# design.net
KiCad netlist of a schematic drawn in EasyEDA Pro
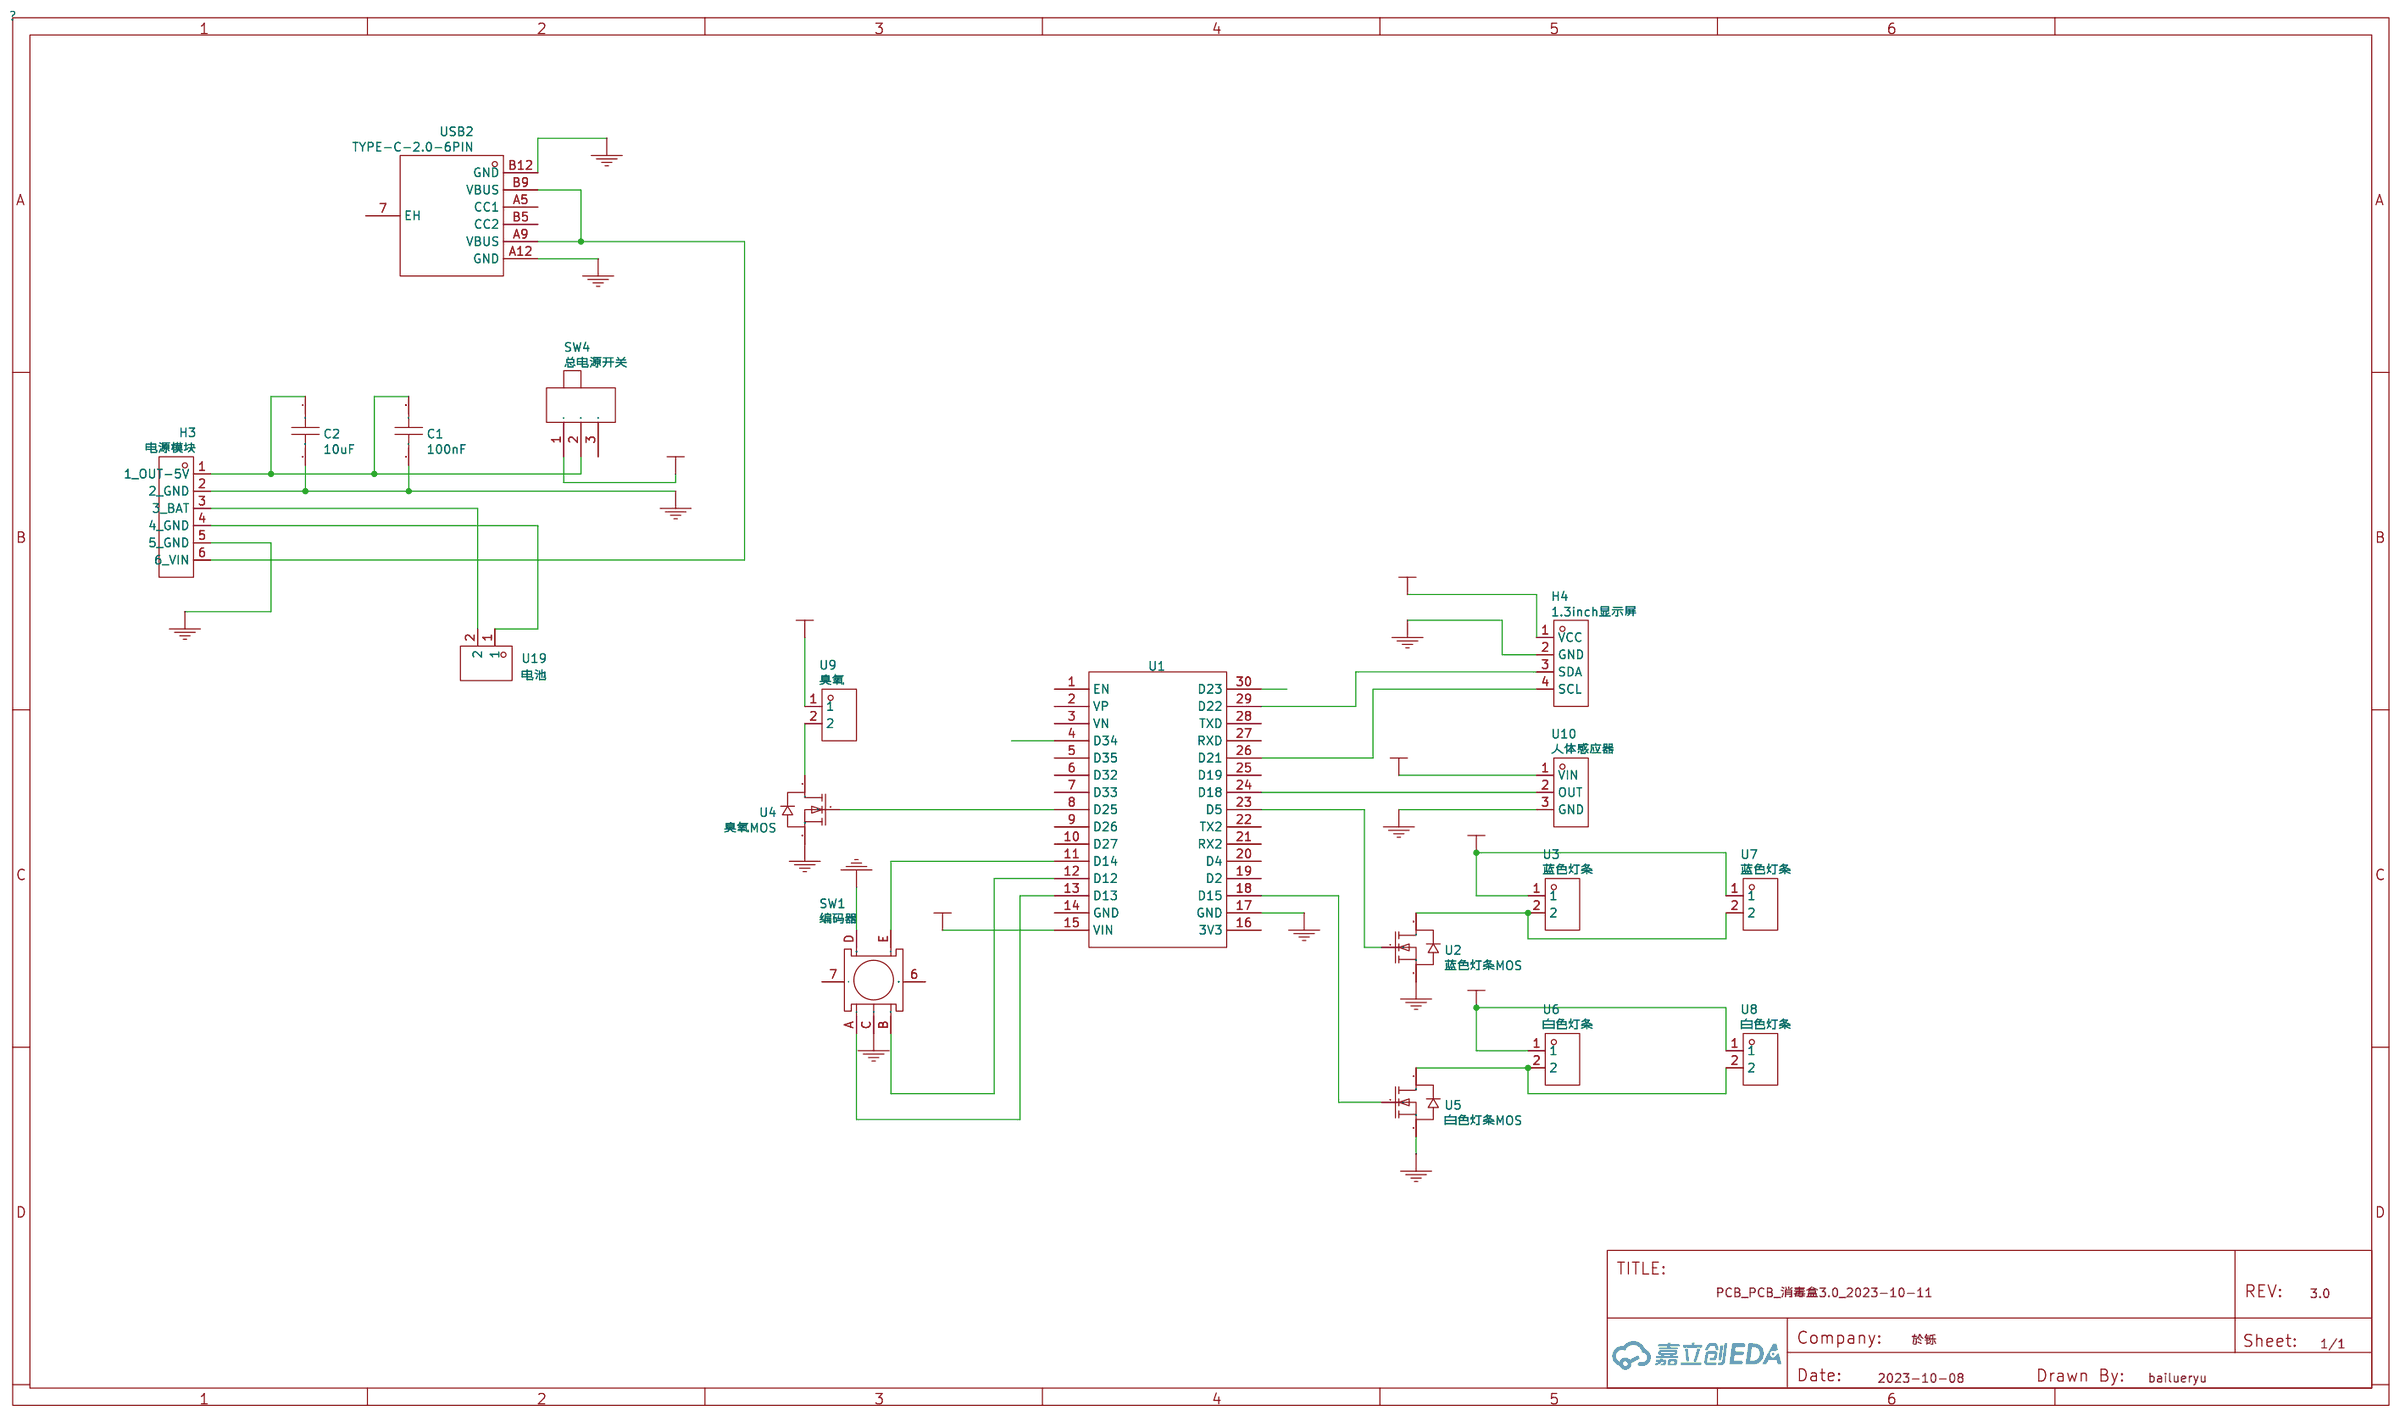
[diagram p0: schematic sheet]

(export (version "E")
  (design (tool "Eeschema 10.0.6"))
  (components
    (comp (ref "C1")
      (value "100nF")
      (footprint "easyedapro:C0603")
      (fields
        (field (name "Manufacturer Part") "MC0603B104K500N8RH")
        (field (name "Manufacturer") "Sunway(信维通信)")
      )
      (libsource (lib "easyedapro") (part "100nF"))
    )
    (comp (ref "C2")
      (value "10uF")
      (footprint "easyedapro:C0603")
      (fields (field (name "Manufacturer") "SAMSUNG(三星)"))
      (libsource (lib "easyedapro") (part "10uF"))
    )
    (comp (ref "H3")
      (value "电源模块")
      (footprint "easyedapro:HDR-TH_6P-P2.54-V-M")
      (fields (field (name "Manufacturer Part") "PZ254V-11-06P") (field (name "Manufacturer") "XFCN(兴飞)"))
      (libsource (lib "easyedapro") (part "电源模块"))
    )
    (comp (ref "H4")
      (value "1.3inch显示屏")
      (footprint "easyedapro:HDR-TH_4P-P2.54-V-M")
      (fields
        (field (name "Manufacturer Part") "KH-2.54PH180-1X4P-L11.5")
        (field (name "Manufacturer") "kinghelm(金航标)")
      )
      (libsource (lib "easyedapro") (part "1.3inch显示屏"))
    )
    (comp (ref "SW1")
      (value "编码器")
      (footprint "easyedapro:SW-TH_EC11E18244A5")
      (fields (field (name "Manufacturer Part") "EC11E18244A5") (field (name "Manufacturer") "ALPS Electric"))
      (libsource (lib "easyedapro") (part "编码器"))
    )
    (comp (ref "SW4")
      (value "总电源开关")
      (footprint "easyedapro:SW-TH_MK-12D18-G040")
      (fields (field (name "Manufacturer Part") "MK-12D18-G020") (field (name "Manufacturer") "G-Switch(品赞)"))
      (libsource (lib "easyedapro") (part "总电源开关"))
    )
    (comp (ref "U1")
      (value "NO")
      (footprint "easyedapro:ESP-WROOM-32")
      (libsource (lib "easyedapro") (part "NO"))
    )
    (comp (ref "U2")
      (value "蓝色灯条MOS")
      (footprint "easyedapro:SOT-23-3_L2.9-W1.3-P1.90-LS2.4-BR")
      (fields (field (name "Manufacturer Part") "5N10") (field (name "Manufacturer") "GOODWORK(固得沃克)"))
      (libsource (lib "easyedapro") (part "蓝色灯条MOS"))
    )
    (comp (ref "U3")
      (value "蓝色灯条")
      (footprint "easyedapro:HDR-TH_2P-P2.00-V-M")
      (fields
        (field (name "Manufacturer Part") "DS1025-01-1x2P8BV1-B")
        (field (name "Manufacturer") "CONNFLY")
      )
      (libsource (lib "easyedapro") (part "蓝色灯条"))
    )
    (comp (ref "U4")
      (value "臭氧MOS")
      (footprint "easyedapro:SOT-23-3_L2.9-W1.3-P1.90-LS2.4-BR")
      (fields (field (name "Manufacturer Part") "5N10") (field (name "Manufacturer") "GOODWORK(固得沃克)"))
      (libsource (lib "easyedapro") (part "臭氧MOS"))
    )
    (comp (ref "U5")
      (value "白色灯条MOS")
      (footprint "easyedapro:SOT-23-3_L2.9-W1.3-P1.90-LS2.4-BR")
      (fields (field (name "Manufacturer Part") "5N10") (field (name "Manufacturer") "GOODWORK(固得沃克)"))
      (libsource (lib "easyedapro") (part "白色灯条MOS"))
    )
    (comp (ref "U6")
      (value "白色灯条")
      (footprint "easyedapro:HDR-TH_2P-P2.00-V-M")
      (fields
        (field (name "Manufacturer Part") "DS1025-01-1x2P8BV1-B")
        (field (name "Manufacturer") "CONNFLY")
      )
      (libsource (lib "easyedapro") (part "白色灯条"))
    )
    (comp (ref "U7")
      (value "蓝色灯条")
      (footprint "easyedapro:HDR-TH_2P-P2.00-V-M")
      (fields
        (field (name "Manufacturer Part") "DS1025-01-1x2P8BV1-B")
        (field (name "Manufacturer") "CONNFLY")
      )
      (libsource (lib "easyedapro") (part "蓝色灯条"))
    )
    (comp (ref "U8")
      (value "白色灯条")
      (footprint "easyedapro:HDR-TH_2P-P2.00-V-M")
      (fields
        (field (name "Manufacturer Part") "DS1025-01-1x2P8BV1-B")
        (field (name "Manufacturer") "CONNFLY")
      )
      (libsource (lib "easyedapro") (part "白色灯条"))
    )
    (comp (ref "U9")
      (value "臭氧")
      (footprint "easyedapro:HDR-TH_2P-P2.00-V-M")
      (fields
        (field (name "Manufacturer Part") "DS1025-01-1x2P8BV1-B")
        (field (name "Manufacturer") "CONNFLY")
      )
      (libsource (lib "easyedapro") (part "臭氧"))
    )
    (comp (ref "U10")
      (value "人体感应器")
      (footprint "easyedapro:HDR-TH_3P-P2.00-V-M")
      (fields
        (field (name "Manufacturer Part") "DS1025-01-1x3P8BV1-B")
        (field (name "Manufacturer") "CONNFLY")
      )
      (libsource (lib "easyedapro") (part "人体感应器"))
    )
    (comp (ref "U19")
      (value "电池")
      (footprint "easyedapro:HDR-TH_2P-P2.00-V-M")
      (fields
        (field (name "Manufacturer Part") "DS1025-01-1x2P8BV1-B")
        (field (name "Manufacturer") "CONNFLY")
      )
      (libsource (lib "easyedapro") (part "臭氧"))
    )
    (comp (ref "USB2")
      (value "TYPE-C-2.0-6PIN")
      (footprint "easyedapro:TYPE-C-SMD_TYPE-C-6P-2")
      (fields (field (name "Manufacturer Part") "Type-C-2.0-6Pin") (field (name "Manufacturer") "CIKI(皓富)"))
      (libsource (lib "easyedapro") (part "TYPE-C-2.0-6PIN"))
    )
  )
  (nets
    (net (code "1") (name "GND") (class "Default")
      (node (ref "C1") (pin "1") (pinfunction "1_1") (pintype "input"))
      (node (ref "C2") (pin "2") (pinfunction "2_2") (pintype "input"))
      (node (ref "H3") (pin "2") (pinfunction "2_GND_2") (pintype "input"))
      (node (ref "H3") (pin "5") (pinfunction "5_GND_5") (pintype "input"))
      (node (ref "H4") (pin "2") (pinfunction "GND_2") (pintype "input"))
      (node (ref "SW1") (pin "C") (pinfunction "C_C") (pintype "input"))
      (node (ref "SW1") (pin "D") (pinfunction "D_D") (pintype "input"))
      (node (ref "U1") (pin "17") (pinfunction "GND_17") (pintype "input"))
      (node (ref "U10") (pin "3") (pinfunction "GND_3") (pintype "input"))
      (node (ref "U2") (pin "2") (pinfunction "S_2") (pintype "input"))
      (node (ref "U4") (pin "2") (pinfunction "S_2") (pintype "input"))
      (node (ref "U5") (pin "2") (pinfunction "S_2") (pintype "input"))
      (node (ref "USB2") (pin "A12") (pinfunction "GND_A12") (pintype "input"))
      (node (ref "USB2") (pin "B12") (pinfunction "GND_B12") (pintype "input"))
    )
    (net (code "2") (name "Net-(H3-1_OUT-5V)") (class "Default")
      (node (ref "C1") (pin "2") (pinfunction "2_2") (pintype "input"))
      (node (ref "C2") (pin "1") (pinfunction "1_1") (pintype "input"))
      (node (ref "H3") (pin "1") (pinfunction "1_OUT-5V_1") (pintype "input"))
      (node (ref "SW4") (pin "2") (pinfunction "2_2") (pintype "input"))
    )
    (net (code "3") (name "Net-(H3-3_BAT)") (class "Default")
      (node (ref "H3") (pin "3") (pinfunction "3_BAT_3") (pintype "input"))
      (node (ref "U19") (pin "2") (pinfunction "2_2") (pintype "input"))
    )
    (net (code "4") (name "Net-(H3-4_GND)") (class "Default")
      (node (ref "H3") (pin "4") (pinfunction "4_GND_4") (pintype "input"))
      (node (ref "U19") (pin "1") (pinfunction "1_1") (pintype "input"))
    )
    (net (code "5") (name "Net-(H3-6_VIN)") (class "Default")
      (node (ref "H3") (pin "6") (pinfunction "6_VIN_6") (pintype "input"))
      (node (ref "USB2") (pin "A9") (pinfunction "VBUS_A9") (pintype "input"))
      (node (ref "USB2") (pin "B9") (pinfunction "VBUS_B9") (pintype "input"))
    )
    (net (code "6") (name "Net-(H4-SCL)") (class "Default")
      (node (ref "H4") (pin "4") (pinfunction "SCL_4") (pintype "input"))
      (node (ref "U1") (pin "26") (pinfunction "D21_26") (pintype "input"))
    )
    (net (code "7") (name "Net-(H4-SDA)") (class "Default")
      (node (ref "H4") (pin "3") (pinfunction "SDA_3") (pintype "input"))
      (node (ref "U1") (pin "29") (pinfunction "D22_29") (pintype "input"))
    )
    (net (code "8") (name "Net-(U1-D5)") (class "Default")
      (node (ref "U1") (pin "23") (pinfunction "D5_23") (pintype "input"))
      (node (ref "U2") (pin "1") (pinfunction "G_1") (pintype "input"))
    )
    (net (code "9") (name "Net-(U1-D12)") (class "Default")
      (node (ref "SW1") (pin "B") (pinfunction "B_B") (pintype "input"))
      (node (ref "U1") (pin "12") (pinfunction "D12_12") (pintype "input"))
    )
    (net (code "10") (name "Net-(U1-D13)") (class "Default")
      (node (ref "SW1") (pin "A") (pinfunction "A_A") (pintype "input"))
      (node (ref "U1") (pin "13") (pinfunction "D13_13") (pintype "input"))
    )
    (net (code "11") (name "Net-(U1-D14)") (class "Default")
      (node (ref "SW1") (pin "E") (pinfunction "E_E") (pintype "input"))
      (node (ref "U1") (pin "11") (pinfunction "D14_11") (pintype "input"))
    )
    (net (code "12") (name "Net-(U1-D15)") (class "Default")
      (node (ref "U1") (pin "18") (pinfunction "D15_18") (pintype "input"))
      (node (ref "U5") (pin "1") (pinfunction "G_1") (pintype "input"))
    )
    (net (code "13") (name "Net-(U1-D18)") (class "Default")
      (node (ref "U1") (pin "24") (pinfunction "D18_24") (pintype "input"))
      (node (ref "U10") (pin "2") (pinfunction "OUT_2") (pintype "input"))
    )
    (net (code "14") (name "Net-(U1-D25)") (class "Default")
      (node (ref "U1") (pin "8") (pinfunction "D25_8") (pintype "input"))
      (node (ref "U4") (pin "1") (pinfunction "G_1") (pintype "input"))
    )
    (net (code "15") (name "Net-(U2-D)") (class "Default")
      (node (ref "U2") (pin "3") (pinfunction "D_3") (pintype "input"))
      (node (ref "U3") (pin "2") (pinfunction "2_2") (pintype "input"))
      (node (ref "U7") (pin "2") (pinfunction "2_2") (pintype "input"))
    )
    (net (code "16") (name "Net-(U4-D)") (class "Default")
      (node (ref "U4") (pin "3") (pinfunction "D_3") (pintype "input"))
      (node (ref "U9") (pin "2") (pinfunction "2_2") (pintype "input"))
    )
    (net (code "17") (name "Net-(U5-D)") (class "Default")
      (node (ref "U5") (pin "3") (pinfunction "D_3") (pintype "input"))
      (node (ref "U6") (pin "2") (pinfunction "2_2") (pintype "input"))
      (node (ref "U8") (pin "2") (pinfunction "2_2") (pintype "input"))
    )
    (net (code "18") (name "VCC") (class "Default")
      (node (ref "H4") (pin "1") (pinfunction "VCC_1") (pintype "input"))
      (node (ref "SW4") (pin "1") (pinfunction "1_1") (pintype "input"))
      (node (ref "U1") (pin "15") (pinfunction "VIN_15") (pintype "input"))
      (node (ref "U10") (pin "1") (pinfunction "VIN_1") (pintype "input"))
      (node (ref "U3") (pin "1") (pinfunction "1_1") (pintype "input"))
      (node (ref "U6") (pin "1") (pinfunction "1_1") (pintype "input"))
      (node (ref "U7") (pin "1") (pinfunction "1_1") (pintype "input"))
      (node (ref "U8") (pin "1") (pinfunction "1_1") (pintype "input"))
      (node (ref "U9") (pin "1") (pinfunction "1_1") (pintype "input"))
    )
    (net (code "19") (name "unconnected-(SW1-Pad6)") (class "Default")
      (node (ref "SW1") (pin "6") (pinfunction "6_6") (pintype "input"))
    )
    (net (code "20") (name "unconnected-(SW1-Pad7)") (class "Default")
      (node (ref "SW1") (pin "7") (pinfunction "7_7") (pintype "input"))
    )
    (net (code "21") (name "unconnected-(SW4-Pad3)") (class "Default")
      (node (ref "SW4") (pin "3") (pinfunction "3_3") (pintype "input"))
    )
    (net (code "22") (name "unconnected-(U1-3V3-Pad16)") (class "Default")
      (node (ref "U1") (pin "16") (pinfunction "3V3_16") (pintype "input"))
    )
    (net (code "23") (name "unconnected-(U1-D2-Pad19)") (class "Default")
      (node (ref "U1") (pin "19") (pinfunction "D2_19") (pintype "input"))
    )
    (net (code "24") (name "unconnected-(U1-D4-Pad20)") (class "Default")
      (node (ref "U1") (pin "20") (pinfunction "D4_20") (pintype "input"))
    )
    (net (code "25") (name "unconnected-(U1-D19-Pad25)") (class "Default")
      (node (ref "U1") (pin "25") (pinfunction "D19_25") (pintype "input"))
    )
    (net (code "26") (name "unconnected-(U1-D23-Pad30)") (class "Default")
      (node (ref "U1") (pin "30") (pinfunction "D23_30") (pintype "input"))
    )
    (net (code "27") (name "unconnected-(U1-D26-Pad9)") (class "Default")
      (node (ref "U1") (pin "9") (pinfunction "D26_9") (pintype "input"))
    )
    (net (code "28") (name "unconnected-(U1-D27-Pad10)") (class "Default")
      (node (ref "U1") (pin "10") (pinfunction "D27_10") (pintype "input"))
    )
    (net (code "29") (name "unconnected-(U1-D32-Pad6)") (class "Default")
      (node (ref "U1") (pin "6") (pinfunction "D32_6") (pintype "input"))
    )
    (net (code "30") (name "unconnected-(U1-D33-Pad7)") (class "Default")
      (node (ref "U1") (pin "7") (pinfunction "D33_7") (pintype "input"))
    )
    (net (code "31") (name "unconnected-(U1-D34-Pad4)") (class "Default")
      (node (ref "U1") (pin "4") (pinfunction "D34_4") (pintype "input"))
    )
    (net (code "32") (name "unconnected-(U1-D35-Pad5)") (class "Default")
      (node (ref "U1") (pin "5") (pinfunction "D35_5") (pintype "input"))
    )
    (net (code "33") (name "unconnected-(U1-EN-Pad1)") (class "Default")
      (node (ref "U1") (pin "1") (pinfunction "EN_1") (pintype "input"))
    )
    (net (code "34") (name "unconnected-(U1-GND-Pad14)") (class "Default")
      (node (ref "U1") (pin "14") (pinfunction "GND_14") (pintype "input"))
    )
    (net (code "35") (name "unconnected-(U1-RX2-Pad21)") (class "Default")
      (node (ref "U1") (pin "21") (pinfunction "RX2_21") (pintype "input"))
    )
    (net (code "36") (name "unconnected-(U1-RXD-Pad27)") (class "Default")
      (node (ref "U1") (pin "27") (pinfunction "RXD_27") (pintype "input"))
    )
    (net (code "37") (name "unconnected-(U1-TX2-Pad22)") (class "Default")
      (node (ref "U1") (pin "22") (pinfunction "TX2_22") (pintype "input"))
    )
    (net (code "38") (name "unconnected-(U1-TXD-Pad28)") (class "Default")
      (node (ref "U1") (pin "28") (pinfunction "TXD_28") (pintype "input"))
    )
    (net (code "39") (name "unconnected-(U1-VN-Pad3)") (class "Default")
      (node (ref "U1") (pin "3") (pinfunction "VN_3") (pintype "input"))
    )
    (net (code "40") (name "unconnected-(U1-VP-Pad2)") (class "Default")
      (node (ref "U1") (pin "2") (pinfunction "VP_2") (pintype "input"))
    )
    (net (code "41") (name "unconnected-(USB2-CC1-PadA5)") (class "Default")
      (node (ref "USB2") (pin "A5") (pinfunction "CC1_A5") (pintype "input"))
    )
    (net (code "42") (name "unconnected-(USB2-CC2-PadB5)") (class "Default")
      (node (ref "USB2") (pin "B5") (pinfunction "CC2_B5") (pintype "input"))
    )
    (net (code "43") (name "unconnected-(USB2-EH-Pad7)") (class "Default")
      (node (ref "USB2") (pin "7") (pinfunction "EH_7") (pintype "input"))
    )
  )
)
